# Stepper_Board.net
KiCad netlist of a schematic drawn in EAGLE
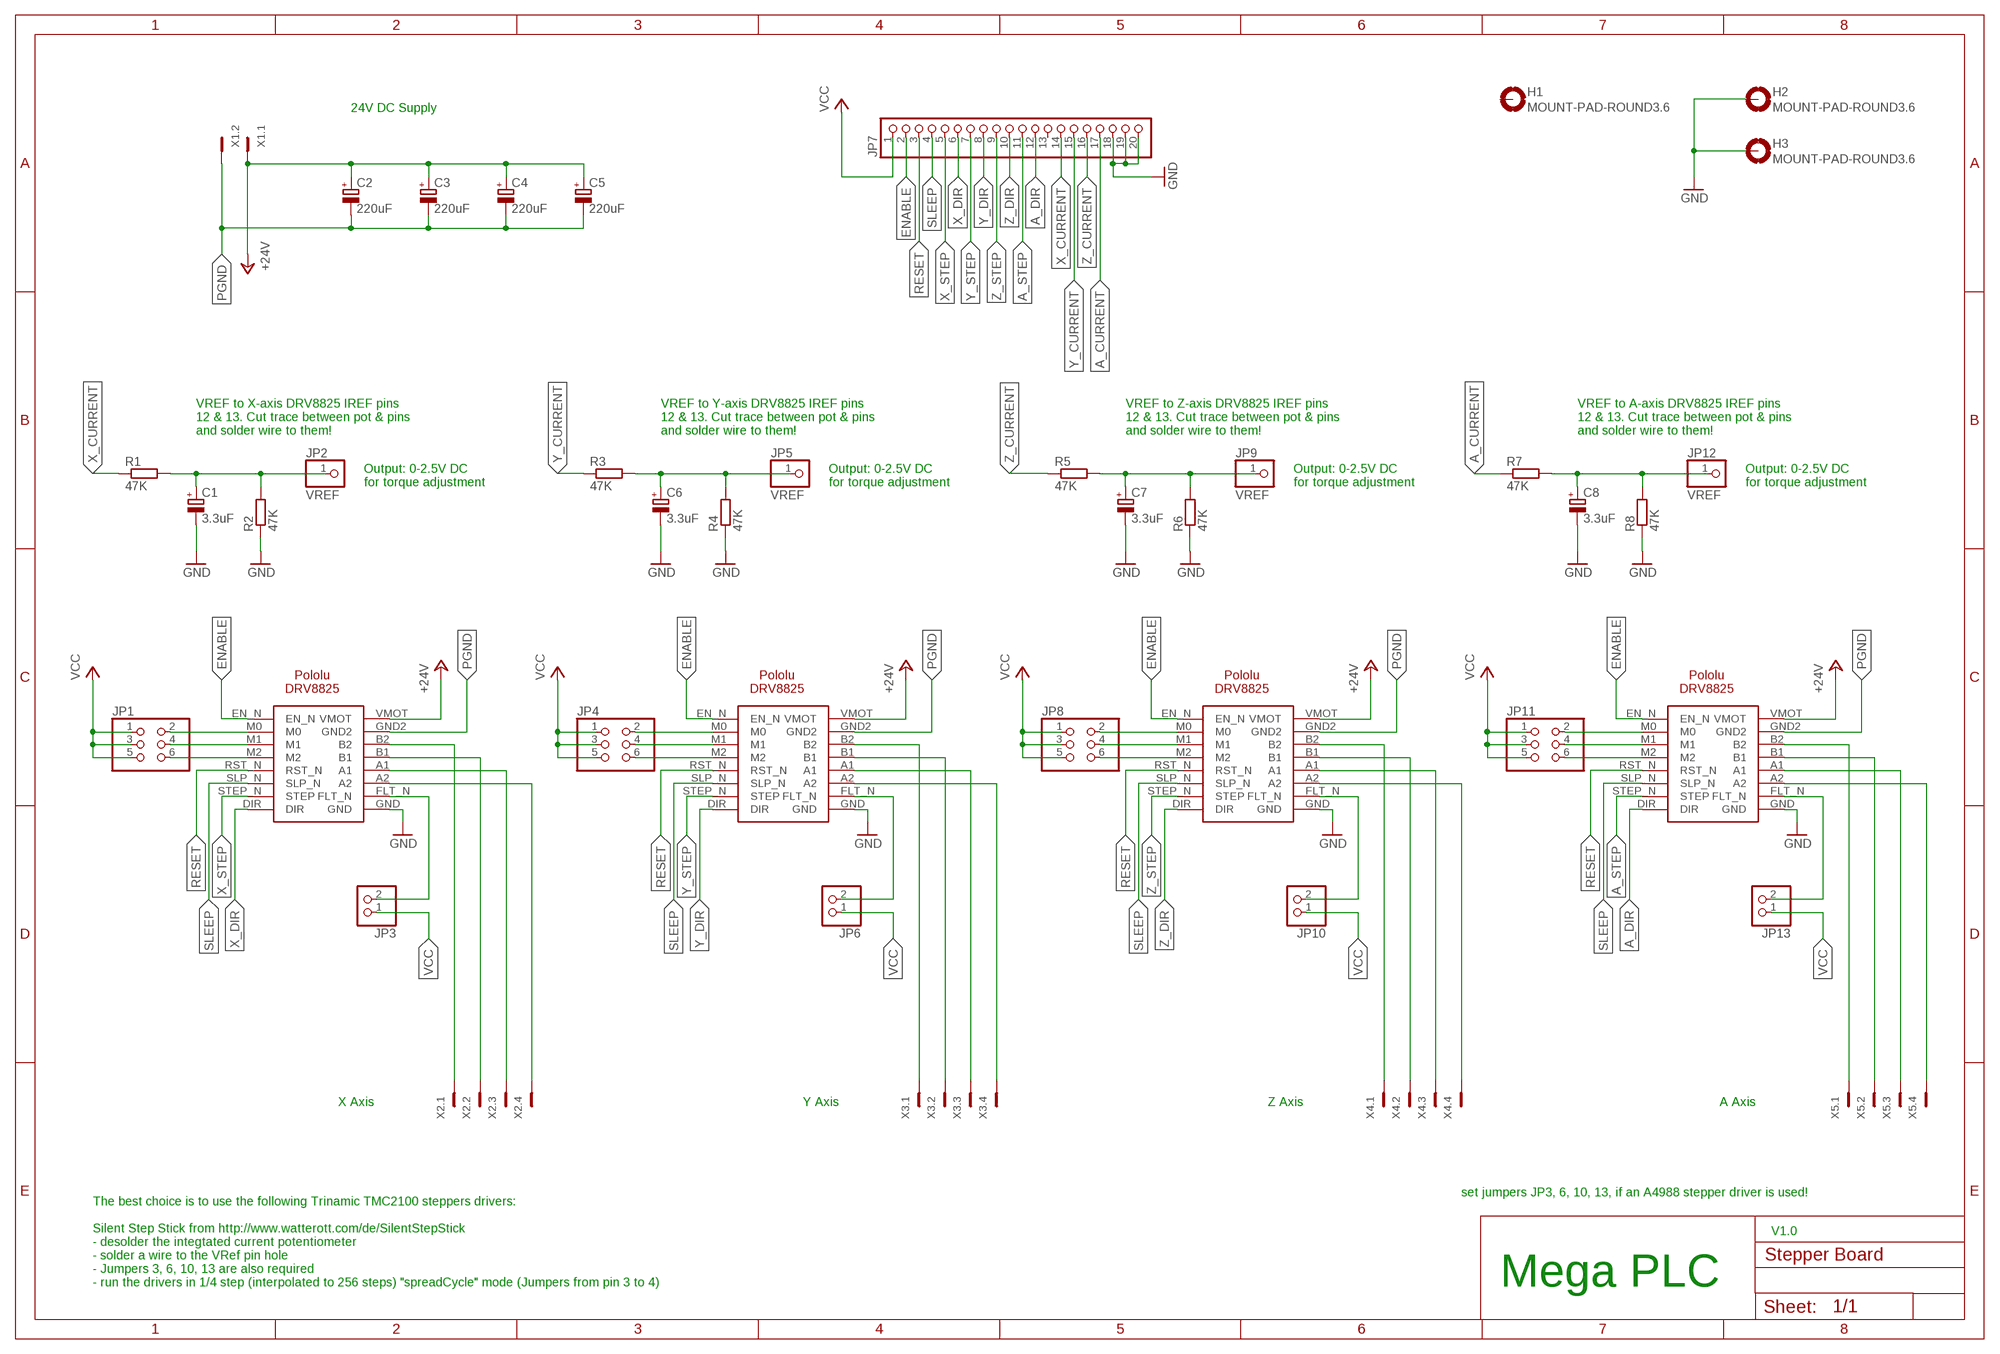
[diagram p0: schematic, sheet 1]

(export (version "E")
  (design (tool "Eeschema 10.0.6"))
  (components
    (comp (ref "C1")
      (value "3.3uF")
      (footprint "eagle-import:B45181A")
      (libsource (lib "eagle-import") (part "CPOL-EUB45181A"))
    )
    (comp (ref "C2")
      (value "220uF")
      (footprint "eagle-import:E5-10,5")
      (libsource (lib "eagle-import") (part "resistor_CPOL-EUE5-10.5"))
    )
    (comp (ref "C3")
      (value "220uF")
      (footprint "eagle-import:E5-10,5")
      (libsource (lib "eagle-import") (part "resistor_CPOL-EUE5-10.5"))
    )
    (comp (ref "C4")
      (value "220uF")
      (footprint "eagle-import:E5-10,5")
      (libsource (lib "eagle-import") (part "resistor_CPOL-EUE5-10.5"))
    )
    (comp (ref "C5")
      (value "220uF")
      (footprint "eagle-import:E5-10,5")
      (libsource (lib "eagle-import") (part "resistor_CPOL-EUE5-10.5"))
    )
    (comp (ref "C6")
      (value "3.3uF")
      (footprint "eagle-import:B45181A")
      (libsource (lib "eagle-import") (part "CPOL-EUB45181A"))
    )
    (comp (ref "C7")
      (value "3.3uF")
      (footprint "eagle-import:B45181A")
      (libsource (lib "eagle-import") (part "CPOL-EUB45181A"))
    )
    (comp (ref "C8")
      (value "3.3uF")
      (footprint "eagle-import:B45181A")
      (libsource (lib "eagle-import") (part "CPOL-EUB45181A"))
    )
    (comp (ref "H1")
      (value "MOUNT-PAD-ROUND3.6")
      (footprint "eagle-import:3,6-PAD")
      (libsource (lib "eagle-import") (part "MOUNT-PAD-ROUND3.6"))
    )
    (comp (ref "H2")
      (value "MOUNT-PAD-ROUND3.6")
      (footprint "eagle-import:3,6-PAD")
      (libsource (lib "eagle-import") (part "MOUNT-PAD-ROUND3.6"))
    )
    (comp (ref "H3")
      (value "MOUNT-PAD-ROUND3.6")
      (footprint "eagle-import:3,6-PAD")
      (libsource (lib "eagle-import") (part "MOUNT-PAD-ROUND3.6"))
    )
    (comp (ref "JP1")
      (value "PINHD-2X3")
      (footprint "eagle-import:2X03")
      (libsource (lib "eagle-import") (part "PINHD-2X3"))
    )
    (comp (ref "JP2")
      (value "VREF")
      (footprint "eagle-import:1X01")
      (libsource (lib "eagle-import") (part "PINHD-1X1"))
    )
    (comp (ref "JP3")
      (value "PINHD-1X2")
      (footprint "eagle-import:1X02")
      (libsource (lib "eagle-import") (part "PINHD-1X2"))
    )
    (comp (ref "JP4")
      (value "PINHD-2X3")
      (footprint "eagle-import:2X03")
      (libsource (lib "eagle-import") (part "PINHD-2X3"))
    )
    (comp (ref "JP5")
      (value "VREF")
      (footprint "eagle-import:1X01")
      (libsource (lib "eagle-import") (part "PINHD-1X1"))
    )
    (comp (ref "JP6")
      (value "PINHD-1X2")
      (footprint "eagle-import:1X02")
      (libsource (lib "eagle-import") (part "PINHD-1X2"))
    )
    (comp (ref "JP7")
      (value "PINHD-1X20/90")
      (footprint "eagle-import:1X20_90")
      (libsource (lib "eagle-import") (part "PINHD-1X20/90"))
    )
    (comp (ref "JP8")
      (value "PINHD-2X3")
      (footprint "eagle-import:2X03")
      (libsource (lib "eagle-import") (part "PINHD-2X3"))
    )
    (comp (ref "JP9")
      (value "VREF")
      (footprint "eagle-import:1X01")
      (libsource (lib "eagle-import") (part "PINHD-1X1"))
    )
    (comp (ref "JP10")
      (value "PINHD-1X2")
      (footprint "eagle-import:1X02")
      (libsource (lib "eagle-import") (part "PINHD-1X2"))
    )
    (comp (ref "JP11")
      (value "PINHD-2X3")
      (footprint "eagle-import:2X03")
      (libsource (lib "eagle-import") (part "PINHD-2X3"))
    )
    (comp (ref "JP12")
      (value "VREF")
      (footprint "eagle-import:1X01")
      (libsource (lib "eagle-import") (part "PINHD-1X1"))
    )
    (comp (ref "JP13")
      (value "PINHD-1X2")
      (footprint "eagle-import:1X02")
      (libsource (lib "eagle-import") (part "PINHD-1X2"))
    )
    (comp (ref "R1")
      (value "47K")
      (footprint "eagle-import:0204_7")
      (libsource (lib "eagle-import") (part "R-EU_0204/7"))
    )
    (comp (ref "R2")
      (value "47K")
      (footprint "eagle-import:0207_15")
      (libsource (lib "eagle-import") (part "R-EU_0207/15"))
    )
    (comp (ref "R3")
      (value "47K")
      (footprint "eagle-import:0207_2V")
      (libsource (lib "eagle-import") (part "R-EU_0207/2V"))
    )
    (comp (ref "R4")
      (value "47K")
      (footprint "eagle-import:0207_15")
      (libsource (lib "eagle-import") (part "R-EU_0207/15"))
    )
    (comp (ref "R5")
      (value "47K")
      (footprint "eagle-import:0207_2V")
      (libsource (lib "eagle-import") (part "R-EU_0207/2V"))
    )
    (comp (ref "R6")
      (value "47K")
      (footprint "eagle-import:0207_15")
      (libsource (lib "eagle-import") (part "R-EU_0207/15"))
    )
    (comp (ref "R7")
      (value "47K")
      (footprint "eagle-import:0207_2V")
      (libsource (lib "eagle-import") (part "R-EU_0207/2V"))
    )
    (comp (ref "R8")
      (value "47K")
      (footprint "eagle-import:0207_15")
      (libsource (lib "eagle-import") (part "R-EU_0207/15"))
    )
    (comp (ref "U1")
      (value "POLOLU-DRV8825")
      (footprint "eagle-import:POLOLU-DRV8825")
      (libsource (lib "eagle-import") (part "POLOLU-DRV8825"))
    )
    (comp (ref "U2")
      (value "POLOLU-DRV8825")
      (footprint "eagle-import:POLOLU-DRV8825")
      (libsource (lib "eagle-import") (part "POLOLU-DRV8825"))
    )
    (comp (ref "U3")
      (value "POLOLU-DRV8825")
      (footprint "eagle-import:POLOLU-DRV8825")
      (libsource (lib "eagle-import") (part "POLOLU-DRV8825"))
    )
    (comp (ref "U4")
      (value "POLOLU-DRV8825")
      (footprint "eagle-import:POLOLU-DRV8825")
      (libsource (lib "eagle-import") (part "POLOLU-DRV8825"))
    )
    (comp (ref "X1")
      (value "MC2")
      (footprint "eagle-import:MC2")
      (libsource (lib "eagle-import") (part "MC2"))
    )
    (comp (ref "X2")
      (value "MC4")
      (footprint "eagle-import:MC4")
      (libsource (lib "eagle-import") (part "MC4"))
    )
    (comp (ref "X3")
      (value "MC4")
      (footprint "eagle-import:MC4")
      (libsource (lib "eagle-import") (part "MC4"))
    )
    (comp (ref "X4")
      (value "MC4")
      (footprint "eagle-import:MC4")
      (libsource (lib "eagle-import") (part "MC4"))
    )
    (comp (ref "X5")
      (value "MC4")
      (footprint "eagle-import:MC4")
      (libsource (lib "eagle-import") (part "MC4"))
    )
  )
  (nets
    (net (code "1") (name "+24V") (class "Default")
      (node (ref "C2") (pin "+") (pinfunction "+_+") (pintype "passive"))
      (node (ref "C3") (pin "+") (pinfunction "+_+") (pintype "passive"))
      (node (ref "C4") (pin "+") (pinfunction "+_+") (pintype "passive"))
      (node (ref "C5") (pin "+") (pinfunction "+_+") (pintype "passive"))
      (node (ref "U1") (pin "VMOT") (pinfunction "VMOT_VMOT") (pintype "bidirectional"))
      (node (ref "U2") (pin "VMOT") (pinfunction "VMOT_VMOT") (pintype "bidirectional"))
      (node (ref "U3") (pin "VMOT") (pinfunction "VMOT_VMOT") (pintype "bidirectional"))
      (node (ref "U4") (pin "VMOT") (pinfunction "VMOT_VMOT") (pintype "bidirectional"))
      (node (ref "X1") (pin "1") (pinfunction "SK_1") (pintype "passive"))
    )
    (net (code "2") (name "A_CURRENT") (class "Default")
      (node (ref "JP7") (pin "17") (pinfunction "17_17") (pintype "passive"))
      (node (ref "R7") (pin "1") (pinfunction "1_1") (pintype "passive"))
    )
    (net (code "3") (name "A_DIR") (class "Default")
      (node (ref "JP7") (pin "12") (pinfunction "12_12") (pintype "passive"))
      (node (ref "U4") (pin "DIR") (pinfunction "DIR_DIR") (pintype "bidirectional"))
    )
    (net (code "4") (name "A_STEP") (class "Default")
      (node (ref "JP7") (pin "11") (pinfunction "11_11") (pintype "passive"))
      (node (ref "U4") (pin "STEP_N") (pinfunction "STEP_STEP_N") (pintype "bidirectional"))
    )
    (net (code "5") (name "ENABLE") (class "Default")
      (node (ref "JP7") (pin "2") (pinfunction "2_2") (pintype "passive"))
      (node (ref "U1") (pin "EN_N") (pinfunction "EN_N_EN_N") (pintype "bidirectional"))
      (node (ref "U2") (pin "EN_N") (pinfunction "EN_N_EN_N") (pintype "bidirectional"))
      (node (ref "U3") (pin "EN_N") (pinfunction "EN_N_EN_N") (pintype "bidirectional"))
      (node (ref "U4") (pin "EN_N") (pinfunction "EN_N_EN_N") (pintype "bidirectional"))
    )
    (net (code "6") (name "GND") (class "Default")
      (node (ref "C1") (pin "-") (pinfunction "-_-") (pintype "passive"))
      (node (ref "C6") (pin "-") (pinfunction "-_-") (pintype "passive"))
      (node (ref "C7") (pin "-") (pinfunction "-_-") (pintype "passive"))
      (node (ref "C8") (pin "-") (pinfunction "-_-") (pintype "passive"))
      (node (ref "H2") (pin "B3,6") (pinfunction "MOUNT_B3,6") (pintype "passive"))
      (node (ref "H3") (pin "B3,6") (pinfunction "MOUNT_B3,6") (pintype "passive"))
      (node (ref "JP7") (pin "18") (pinfunction "18_18") (pintype "passive"))
      (node (ref "JP7") (pin "19") (pinfunction "19_19") (pintype "passive"))
      (node (ref "JP7") (pin "20") (pinfunction "20_20") (pintype "passive"))
      (node (ref "R2") (pin "1") (pinfunction "1_1") (pintype "passive"))
      (node (ref "R4") (pin "1") (pinfunction "1_1") (pintype "passive"))
      (node (ref "R6") (pin "1") (pinfunction "1_1") (pintype "passive"))
      (node (ref "R8") (pin "1") (pinfunction "1_1") (pintype "passive"))
      (node (ref "U1") (pin "GND") (pinfunction "GND_GND") (pintype "bidirectional"))
      (node (ref "U2") (pin "GND") (pinfunction "GND_GND") (pintype "bidirectional"))
      (node (ref "U3") (pin "GND") (pinfunction "GND_GND") (pintype "bidirectional"))
      (node (ref "U4") (pin "GND") (pinfunction "GND_GND") (pintype "bidirectional"))
    )
    (net (code "7") (name "Net-(C1-Pad+)") (class "Default")
      (node (ref "C1") (pin "+") (pinfunction "+_+") (pintype "passive"))
      (node (ref "JP2") (pin "1") (pinfunction "1_1") (pintype "passive"))
      (node (ref "R1") (pin "2") (pinfunction "2_2") (pintype "passive"))
      (node (ref "R2") (pin "2") (pinfunction "2_2") (pintype "passive"))
    )
    (net (code "8") (name "Net-(C6-Pad+)") (class "Default")
      (node (ref "C6") (pin "+") (pinfunction "+_+") (pintype "passive"))
      (node (ref "JP5") (pin "1") (pinfunction "1_1") (pintype "passive"))
      (node (ref "R3") (pin "2") (pinfunction "2_2") (pintype "passive"))
      (node (ref "R4") (pin "2") (pinfunction "2_2") (pintype "passive"))
    )
    (net (code "9") (name "Net-(C7-Pad+)") (class "Default")
      (node (ref "C7") (pin "+") (pinfunction "+_+") (pintype "passive"))
      (node (ref "JP9") (pin "1") (pinfunction "1_1") (pintype "passive"))
      (node (ref "R5") (pin "2") (pinfunction "2_2") (pintype "passive"))
      (node (ref "R6") (pin "2") (pinfunction "2_2") (pintype "passive"))
    )
    (net (code "10") (name "Net-(C8-Pad+)") (class "Default")
      (node (ref "C8") (pin "+") (pinfunction "+_+") (pintype "passive"))
      (node (ref "JP12") (pin "1") (pinfunction "1_1") (pintype "passive"))
      (node (ref "R7") (pin "2") (pinfunction "2_2") (pintype "passive"))
      (node (ref "R8") (pin "2") (pinfunction "2_2") (pintype "passive"))
    )
    (net (code "11") (name "Net-(JP1-Pad2)") (class "Default")
      (node (ref "JP1") (pin "2") (pinfunction "2_2") (pintype "passive"))
      (node (ref "U1") (pin "M0") (pinfunction "M0_M0") (pintype "bidirectional"))
    )
    (net (code "12") (name "Net-(JP1-Pad4)") (class "Default")
      (node (ref "JP1") (pin "4") (pinfunction "4_4") (pintype "passive"))
      (node (ref "U1") (pin "M1") (pinfunction "M1_M1") (pintype "bidirectional"))
    )
    (net (code "13") (name "Net-(JP1-Pad6)") (class "Default")
      (node (ref "JP1") (pin "6") (pinfunction "6_6") (pintype "passive"))
      (node (ref "U1") (pin "M2") (pinfunction "M2_M2") (pintype "bidirectional"))
    )
    (net (code "14") (name "Net-(JP3-Pad2)") (class "Default")
      (node (ref "JP3") (pin "2") (pinfunction "2_2") (pintype "passive"))
      (node (ref "U1") (pin "FLT_N") (pinfunction "FLT_N_FLT_N") (pintype "bidirectional"))
    )
    (net (code "15") (name "Net-(JP4-Pad2)") (class "Default")
      (node (ref "JP4") (pin "2") (pinfunction "2_2") (pintype "passive"))
      (node (ref "U2") (pin "M0") (pinfunction "M0_M0") (pintype "bidirectional"))
    )
    (net (code "16") (name "Net-(JP4-Pad4)") (class "Default")
      (node (ref "JP4") (pin "4") (pinfunction "4_4") (pintype "passive"))
      (node (ref "U2") (pin "M1") (pinfunction "M1_M1") (pintype "bidirectional"))
    )
    (net (code "17") (name "Net-(JP4-Pad6)") (class "Default")
      (node (ref "JP4") (pin "6") (pinfunction "6_6") (pintype "passive"))
      (node (ref "U2") (pin "M2") (pinfunction "M2_M2") (pintype "bidirectional"))
    )
    (net (code "18") (name "Net-(JP6-Pad2)") (class "Default")
      (node (ref "JP6") (pin "2") (pinfunction "2_2") (pintype "passive"))
      (node (ref "U2") (pin "FLT_N") (pinfunction "FLT_N_FLT_N") (pintype "bidirectional"))
    )
    (net (code "19") (name "Net-(JP8-Pad2)") (class "Default")
      (node (ref "JP8") (pin "2") (pinfunction "2_2") (pintype "passive"))
      (node (ref "U3") (pin "M0") (pinfunction "M0_M0") (pintype "bidirectional"))
    )
    (net (code "20") (name "Net-(JP8-Pad4)") (class "Default")
      (node (ref "JP8") (pin "4") (pinfunction "4_4") (pintype "passive"))
      (node (ref "U3") (pin "M1") (pinfunction "M1_M1") (pintype "bidirectional"))
    )
    (net (code "21") (name "Net-(JP8-Pad6)") (class "Default")
      (node (ref "JP8") (pin "6") (pinfunction "6_6") (pintype "passive"))
      (node (ref "U3") (pin "M2") (pinfunction "M2_M2") (pintype "bidirectional"))
    )
    (net (code "22") (name "Net-(JP10-Pad2)") (class "Default")
      (node (ref "JP10") (pin "2") (pinfunction "2_2") (pintype "passive"))
      (node (ref "U3") (pin "FLT_N") (pinfunction "FLT_N_FLT_N") (pintype "bidirectional"))
    )
    (net (code "23") (name "Net-(JP11-Pad2)") (class "Default")
      (node (ref "JP11") (pin "2") (pinfunction "2_2") (pintype "passive"))
      (node (ref "U4") (pin "M0") (pinfunction "M0_M0") (pintype "bidirectional"))
    )
    (net (code "24") (name "Net-(JP11-Pad4)") (class "Default")
      (node (ref "JP11") (pin "4") (pinfunction "4_4") (pintype "passive"))
      (node (ref "U4") (pin "M1") (pinfunction "M1_M1") (pintype "bidirectional"))
    )
    (net (code "25") (name "Net-(JP11-Pad6)") (class "Default")
      (node (ref "JP11") (pin "6") (pinfunction "6_6") (pintype "passive"))
      (node (ref "U4") (pin "M2") (pinfunction "M2_M2") (pintype "bidirectional"))
    )
    (net (code "26") (name "Net-(JP13-Pad2)") (class "Default")
      (node (ref "JP13") (pin "2") (pinfunction "2_2") (pintype "passive"))
      (node (ref "U4") (pin "FLT_N") (pinfunction "FLT_N_FLT_N") (pintype "bidirectional"))
    )
    (net (code "27") (name "Net-(X2A-SK)") (class "Default")
      (node (ref "U1") (pin "B2") (pinfunction "B2_B2") (pintype "bidirectional"))
      (node (ref "X2") (pin "1") (pinfunction "SK_1") (pintype "passive"))
    )
    (net (code "28") (name "Net-(X2B-SK)") (class "Default")
      (node (ref "U1") (pin "B1") (pinfunction "B1_B1") (pintype "bidirectional"))
      (node (ref "X2") (pin "2") (pinfunction "SK_2") (pintype "passive"))
    )
    (net (code "29") (name "Net-(X2C-SK)") (class "Default")
      (node (ref "U1") (pin "A1") (pinfunction "A1_A1") (pintype "bidirectional"))
      (node (ref "X2") (pin "3") (pinfunction "SK_3") (pintype "passive"))
    )
    (net (code "30") (name "Net-(X2D-SK)") (class "Default")
      (node (ref "U1") (pin "A2") (pinfunction "A2_A2") (pintype "bidirectional"))
      (node (ref "X2") (pin "4") (pinfunction "SK_4") (pintype "passive"))
    )
    (net (code "31") (name "Net-(X3A-SK)") (class "Default")
      (node (ref "U2") (pin "B2") (pinfunction "B2_B2") (pintype "bidirectional"))
      (node (ref "X3") (pin "1") (pinfunction "SK_1") (pintype "passive"))
    )
    (net (code "32") (name "Net-(X3B-SK)") (class "Default")
      (node (ref "U2") (pin "B1") (pinfunction "B1_B1") (pintype "bidirectional"))
      (node (ref "X3") (pin "2") (pinfunction "SK_2") (pintype "passive"))
    )
    (net (code "33") (name "Net-(X3C-SK)") (class "Default")
      (node (ref "U2") (pin "A1") (pinfunction "A1_A1") (pintype "bidirectional"))
      (node (ref "X3") (pin "3") (pinfunction "SK_3") (pintype "passive"))
    )
    (net (code "34") (name "Net-(X3D-SK)") (class "Default")
      (node (ref "U2") (pin "A2") (pinfunction "A2_A2") (pintype "bidirectional"))
      (node (ref "X3") (pin "4") (pinfunction "SK_4") (pintype "passive"))
    )
    (net (code "35") (name "Net-(X4A-SK)") (class "Default")
      (node (ref "U3") (pin "B2") (pinfunction "B2_B2") (pintype "bidirectional"))
      (node (ref "X4") (pin "1") (pinfunction "SK_1") (pintype "passive"))
    )
    (net (code "36") (name "Net-(X4B-SK)") (class "Default")
      (node (ref "U3") (pin "B1") (pinfunction "B1_B1") (pintype "bidirectional"))
      (node (ref "X4") (pin "2") (pinfunction "SK_2") (pintype "passive"))
    )
    (net (code "37") (name "Net-(X4C-SK)") (class "Default")
      (node (ref "U3") (pin "A1") (pinfunction "A1_A1") (pintype "bidirectional"))
      (node (ref "X4") (pin "3") (pinfunction "SK_3") (pintype "passive"))
    )
    (net (code "38") (name "Net-(X4D-SK)") (class "Default")
      (node (ref "U3") (pin "A2") (pinfunction "A2_A2") (pintype "bidirectional"))
      (node (ref "X4") (pin "4") (pinfunction "SK_4") (pintype "passive"))
    )
    (net (code "39") (name "Net-(X5A-SK)") (class "Default")
      (node (ref "U4") (pin "B2") (pinfunction "B2_B2") (pintype "bidirectional"))
      (node (ref "X5") (pin "1") (pinfunction "SK_1") (pintype "passive"))
    )
    (net (code "40") (name "Net-(X5B-SK)") (class "Default")
      (node (ref "U4") (pin "B1") (pinfunction "B1_B1") (pintype "bidirectional"))
      (node (ref "X5") (pin "2") (pinfunction "SK_2") (pintype "passive"))
    )
    (net (code "41") (name "Net-(X5C-SK)") (class "Default")
      (node (ref "U4") (pin "A1") (pinfunction "A1_A1") (pintype "bidirectional"))
      (node (ref "X5") (pin "3") (pinfunction "SK_3") (pintype "passive"))
    )
    (net (code "42") (name "Net-(X5D-SK)") (class "Default")
      (node (ref "U4") (pin "A2") (pinfunction "A2_A2") (pintype "bidirectional"))
      (node (ref "X5") (pin "4") (pinfunction "SK_4") (pintype "passive"))
    )
    (net (code "43") (name "PGND") (class "Default")
      (node (ref "C2") (pin "-") (pinfunction "-_-") (pintype "passive"))
      (node (ref "C3") (pin "-") (pinfunction "-_-") (pintype "passive"))
      (node (ref "C4") (pin "-") (pinfunction "-_-") (pintype "passive"))
      (node (ref "C5") (pin "-") (pinfunction "-_-") (pintype "passive"))
      (node (ref "U1") (pin "GND2") (pinfunction "GND2_GND2") (pintype "bidirectional"))
      (node (ref "U2") (pin "GND2") (pinfunction "GND2_GND2") (pintype "bidirectional"))
      (node (ref "U3") (pin "GND2") (pinfunction "GND2_GND2") (pintype "bidirectional"))
      (node (ref "U4") (pin "GND2") (pinfunction "GND2_GND2") (pintype "bidirectional"))
      (node (ref "X1") (pin "2") (pinfunction "SK_2") (pintype "passive"))
    )
    (net (code "44") (name "RESET") (class "Default")
      (node (ref "JP7") (pin "3") (pinfunction "3_3") (pintype "passive"))
      (node (ref "U1") (pin "RST_N") (pinfunction "RST_N_RST_N") (pintype "bidirectional"))
      (node (ref "U2") (pin "RST_N") (pinfunction "RST_N_RST_N") (pintype "bidirectional"))
      (node (ref "U3") (pin "RST_N") (pinfunction "RST_N_RST_N") (pintype "bidirectional"))
      (node (ref "U4") (pin "RST_N") (pinfunction "RST_N_RST_N") (pintype "bidirectional"))
    )
    (net (code "45") (name "SLEEP") (class "Default")
      (node (ref "JP7") (pin "4") (pinfunction "4_4") (pintype "passive"))
      (node (ref "U1") (pin "SLP_N") (pinfunction "SLP_N_SLP_N") (pintype "bidirectional"))
      (node (ref "U2") (pin "SLP_N") (pinfunction "SLP_N_SLP_N") (pintype "bidirectional"))
      (node (ref "U3") (pin "SLP_N") (pinfunction "SLP_N_SLP_N") (pintype "bidirectional"))
      (node (ref "U4") (pin "SLP_N") (pinfunction "SLP_N_SLP_N") (pintype "bidirectional"))
    )
    (net (code "46") (name "VCC") (class "Default")
      (node (ref "JP1") (pin "1") (pinfunction "1_1") (pintype "passive"))
      (node (ref "JP1") (pin "3") (pinfunction "3_3") (pintype "passive"))
      (node (ref "JP1") (pin "5") (pinfunction "5_5") (pintype "passive"))
      (node (ref "JP10") (pin "1") (pinfunction "1_1") (pintype "passive"))
      (node (ref "JP11") (pin "1") (pinfunction "1_1") (pintype "passive"))
      (node (ref "JP11") (pin "3") (pinfunction "3_3") (pintype "passive"))
      (node (ref "JP11") (pin "5") (pinfunction "5_5") (pintype "passive"))
      (node (ref "JP13") (pin "1") (pinfunction "1_1") (pintype "passive"))
      (node (ref "JP3") (pin "1") (pinfunction "1_1") (pintype "passive"))
      (node (ref "JP4") (pin "1") (pinfunction "1_1") (pintype "passive"))
      (node (ref "JP4") (pin "3") (pinfunction "3_3") (pintype "passive"))
      (node (ref "JP4") (pin "5") (pinfunction "5_5") (pintype "passive"))
      (node (ref "JP6") (pin "1") (pinfunction "1_1") (pintype "passive"))
      (node (ref "JP7") (pin "1") (pinfunction "1_1") (pintype "passive"))
      (node (ref "JP8") (pin "1") (pinfunction "1_1") (pintype "passive"))
      (node (ref "JP8") (pin "3") (pinfunction "3_3") (pintype "passive"))
      (node (ref "JP8") (pin "5") (pinfunction "5_5") (pintype "passive"))
    )
    (net (code "47") (name "X_CURRENT") (class "Default")
      (node (ref "JP7") (pin "14") (pinfunction "14_14") (pintype "passive"))
      (node (ref "R1") (pin "1") (pinfunction "1_1") (pintype "passive"))
    )
    (net (code "48") (name "X_DIR") (class "Default")
      (node (ref "JP7") (pin "6") (pinfunction "6_6") (pintype "passive"))
      (node (ref "U1") (pin "DIR") (pinfunction "DIR_DIR") (pintype "bidirectional"))
    )
    (net (code "49") (name "X_STEP") (class "Default")
      (node (ref "JP7") (pin "5") (pinfunction "5_5") (pintype "passive"))
      (node (ref "U1") (pin "STEP_N") (pinfunction "STEP_STEP_N") (pintype "bidirectional"))
    )
    (net (code "50") (name "Y_CURRENT") (class "Default")
      (node (ref "JP7") (pin "15") (pinfunction "15_15") (pintype "passive"))
      (node (ref "R3") (pin "1") (pinfunction "1_1") (pintype "passive"))
    )
    (net (code "51") (name "Y_DIR") (class "Default")
      (node (ref "JP7") (pin "8") (pinfunction "8_8") (pintype "passive"))
      (node (ref "U2") (pin "DIR") (pinfunction "DIR_DIR") (pintype "bidirectional"))
    )
    (net (code "52") (name "Y_STEP") (class "Default")
      (node (ref "JP7") (pin "7") (pinfunction "7_7") (pintype "passive"))
      (node (ref "U2") (pin "STEP_N") (pinfunction "STEP_STEP_N") (pintype "bidirectional"))
    )
    (net (code "53") (name "Z_CURRENT") (class "Default")
      (node (ref "JP7") (pin "16") (pinfunction "16_16") (pintype "passive"))
      (node (ref "R5") (pin "1") (pinfunction "1_1") (pintype "passive"))
    )
    (net (code "54") (name "Z_DIR") (class "Default")
      (node (ref "JP7") (pin "10") (pinfunction "10_10") (pintype "passive"))
      (node (ref "U3") (pin "DIR") (pinfunction "DIR_DIR") (pintype "bidirectional"))
    )
    (net (code "55") (name "Z_STEP") (class "Default")
      (node (ref "JP7") (pin "9") (pinfunction "9_9") (pintype "passive"))
      (node (ref "U3") (pin "STEP_N") (pinfunction "STEP_STEP_N") (pintype "bidirectional"))
    )
    (net (code "56") (name "unconnected-(H1-MOUNT-PadB3,6)") (class "Default")
      (node (ref "H1") (pin "B3,6") (pinfunction "MOUNT_B3,6") (pintype "passive"))
    )
    (net (code "57") (name "unconnected-(JP7-Pad13)") (class "Default")
      (node (ref "JP7") (pin "13") (pinfunction "13_13") (pintype "passive"))
    )
  )
)
